# Roseta_Battery.net
KiCad netlist of a schematic drawn in Altium Designer
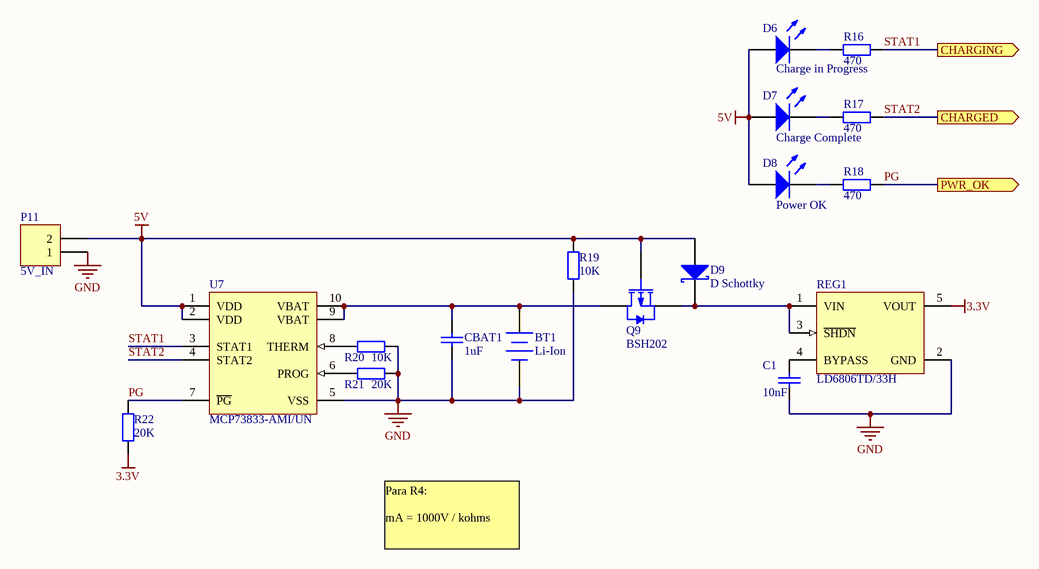
[diagram p0: Roseta_Battery.SchDoc]

(export (version "E")
  (design (tool "Eeschema 10.0.6"))
  (components
    (comp (ref "BT1")
      (value "Li-Ion")
      (footprint "BAT-2")
      (description "Multicell Battery")
      (fields (field (name "PUBLISHER") "Altium Limited"))
      (libsource (lib "Miscellaneous Devices") (part "Battery"))
    )
    (comp (ref "C1")
      (value "10nF")
      (footprint "1608[0603]")
      (description "Capacitor")
      (fields (field (name "Comment") "Cap") (field (name "PUBLISHER") "Altium Limited"))
      (libsource (lib "Miscellaneous Devices") (part "Cap"))
    )
    (comp (ref "CBAT1")
      (value "1uF")
      (footprint "1608[0603]")
      (description "Capacitor")
      (fields (field (name "Comment") "Cap") (field (name "PUBLISHER") "Altium Limited"))
      (libsource (lib "Miscellaneous Devices") (part "Cap"))
    )
    (comp (ref "D6")
      (value "Charge in Progress")
      (footprint "2013[0805]")
      (libsource (lib "LibreriaComponentes") (part "LED SMD (0603)"))
    )
    (comp (ref "D7")
      (value "Charge Complete")
      (footprint "2013[0805]")
      (libsource (lib "LibreriaComponentes") (part "LED SMD (0603)"))
    )
    (comp (ref "D8")
      (value "Power OK")
      (footprint "2013[0805]")
      (libsource (lib "LibreriaComponentes") (part "LED SMD (0603)"))
    )
    (comp (ref "D9")
      (value "D Schottky")
      (footprint "SOD123/X.85")
      (description "Schottky Diode")
      (fields (field (name "PUBLISHER") "Altium Limited"))
      (libsource (lib "Miscellaneous Devices") (part "D Schottky"))
    )
    (comp (ref "P11")
      (value "5V_IN")
      (footprint "HDR1X2")
      (description "Header, 2-Pin")
      (fields (field (name "PUBLISHER") "Altium Limited"))
      (libsource (lib "Miscellaneous Connectors") (part "Header 2"))
    )
    (comp (ref "Q9")
      (value "BSH202")
      (footprint "SOT95P240-3M")
      (description "P-channel Enhancement Mode MOSFET")
      (fields (field (name "PUBLISHER") "Altium Limited"))
      (libsource (lib "Philips Discrete MOSFET - Low Power") (part "BSH202"))
    )
    (comp (ref "R16")
      (value "470")
      (footprint "1608[0603]")
      (description "Resistor")
      (fields (field (name "Comment") "Res2") (field (name "PUBLISHER") "Altium Limited"))
      (libsource (lib "Miscellaneous Devices") (part "Res2"))
    )
    (comp (ref "R17")
      (value "470")
      (footprint "1608[0603]")
      (description "Resistor")
      (fields (field (name "Comment") "Res2") (field (name "PUBLISHER") "Altium Limited"))
      (libsource (lib "Miscellaneous Devices") (part "Res2"))
    )
    (comp (ref "R18")
      (value "470")
      (footprint "1608[0603]")
      (description "Resistor")
      (fields (field (name "Comment") "Res2") (field (name "PUBLISHER") "Altium Limited"))
      (libsource (lib "Miscellaneous Devices") (part "Res2"))
    )
    (comp (ref "R19")
      (value "10K")
      (footprint "1608[0603]")
      (description "Resistor")
      (fields (field (name "Comment") "Res2") (field (name "PUBLISHER") "Altium Limited"))
      (libsource (lib "") (part "Res2_1"))
    )
    (comp (ref "R20")
      (value "10K")
      (footprint "1608[0603]")
      (description "Resistor")
      (fields (field (name "Comment") "Res2") (field (name "PUBLISHER") "Altium Limited"))
      (libsource (lib "") (part "Res2_2"))
    )
    (comp (ref "R21")
      (value "20K")
      (footprint "1608[0603]")
      (description "Resistor")
      (fields (field (name "Comment") "Res2") (field (name "PUBLISHER") "Altium Limited"))
      (libsource (lib "") (part "Res2_2"))
    )
    (comp (ref "R22")
      (value "20K")
      (footprint "1608[0603]")
      (description "Resistor")
      (fields (field (name "Comment") "Res2") (field (name "PUBLISHER") "Altium Limited"))
      (libsource (lib "") (part "Res2_1"))
    )
    (comp (ref "REG1")
      (value "LD6806TD/33H")
      (footprint "SOT-23-OT5_N")
      (fields (field (name "PUBLISHER") "Altium Limited"))
      (libsource (lib "Microchip Power Mgt Line Regulator") (part "TC1014-1.8VCT713"))
    )
    (comp (ref "U7")
      (value "MCP73833-AMI/UN")
      (footprint "MSOP-UN10_N")
      (fields (field (name "PUBLISHER") "Altium Limited"))
      (libsource (lib "Microchip Power Mgt Battery Management") (part "MCP73833-AMI/UN"))
    )
  )
  (nets
    (net (code "1") (name "/PG") (class "Default")
      (node (ref "R18") (pin "2") (pinfunction "2_2") (pintype "passive"))
      (node (ref "R22") (pin "1") (pinfunction "1_1") (pintype "passive"))
      (node (ref "U7") (pin "7") (pinfunction "~{PG}_7") (pintype "open_collector"))
    )
    (net (code "2") (name "/STAT1") (class "Default")
      (node (ref "R16") (pin "2") (pinfunction "2_2") (pintype "passive"))
      (node (ref "U7") (pin "3") (pinfunction "STAT1_3") (pintype "open_collector"))
    )
    (net (code "3") (name "/STAT2") (class "Default")
      (node (ref "R17") (pin "2") (pinfunction "2_2") (pintype "passive"))
      (node (ref "U7") (pin "4") (pinfunction "STAT2_4") (pintype "open_collector"))
    )
    (net (code "4") (name "3.3V") (class "Default")
      (node (ref "R22") (pin "2") (pinfunction "2_2") (pintype "passive"))
      (node (ref "REG1") (pin "5") (pinfunction "VOUT_5") (pintype "power_in"))
    )
    (net (code "5") (name "5V") (class "Default")
      (node (ref "D6") (pin "1") (pinfunction "1_1") (pintype "passive"))
      (node (ref "D7") (pin "1") (pinfunction "1_1") (pintype "passive"))
      (node (ref "D8") (pin "1") (pinfunction "1_1") (pintype "passive"))
      (node (ref "D9") (pin "1") (pinfunction "A_1") (pintype "passive"))
      (node (ref "P11") (pin "2") (pinfunction "2_2") (pintype "passive"))
      (node (ref "Q9") (pin "1") (pinfunction "G_1") (pintype "passive"))
      (node (ref "R19") (pin "1") (pinfunction "1_1") (pintype "passive"))
      (node (ref "U7") (pin "1") (pinfunction "VDD_1") (pintype "power_in"))
      (node (ref "U7") (pin "2") (pinfunction "VDD_2") (pintype "power_in"))
    )
    (net (code "6") (name "GND") (class "Default")
      (node (ref "BT1") (pin "2") (pinfunction "-_2") (pintype "passive"))
      (node (ref "C1") (pin "1") (pinfunction "1_1") (pintype "passive"))
      (node (ref "CBAT1") (pin "2") (pinfunction "2_2") (pintype "passive"))
      (node (ref "P11") (pin "1") (pinfunction "1_1") (pintype "passive"))
      (node (ref "R19") (pin "2") (pinfunction "2_2") (pintype "passive"))
      (node (ref "R20") (pin "1") (pinfunction "1_1") (pintype "passive"))
      (node (ref "R21") (pin "1") (pinfunction "1_1") (pintype "passive"))
      (node (ref "REG1") (pin "2") (pinfunction "GND_2") (pintype "power_in"))
      (node (ref "U7") (pin "5") (pinfunction "VSS_5") (pintype "power_in"))
    )
    (net (code "7") (name "Net-(BT1-+)") (class "Default")
      (node (ref "BT1") (pin "1") (pinfunction "+_1") (pintype "passive"))
      (node (ref "CBAT1") (pin "1") (pinfunction "1_1") (pintype "passive"))
      (node (ref "Q9") (pin "3") (pinfunction "D_3") (pintype "passive"))
      (node (ref "U7") (pin "10") (pinfunction "VBAT_10") (pintype "power_in"))
      (node (ref "U7") (pin "9") (pinfunction "VBAT_9") (pintype "power_in"))
    )
    (net (code "8") (name "Net-(D6-Pad2)") (class "Default")
      (node (ref "D6") (pin "2") (pinfunction "2_2") (pintype "passive"))
      (node (ref "R16") (pin "1") (pinfunction "1_1") (pintype "passive"))
    )
    (net (code "9") (name "Net-(D7-Pad2)") (class "Default")
      (node (ref "D7") (pin "2") (pinfunction "2_2") (pintype "passive"))
      (node (ref "R17") (pin "1") (pinfunction "1_1") (pintype "passive"))
    )
    (net (code "10") (name "Net-(D8-Pad2)") (class "Default")
      (node (ref "D8") (pin "2") (pinfunction "2_2") (pintype "passive"))
      (node (ref "R18") (pin "1") (pinfunction "1_1") (pintype "passive"))
    )
    (net (code "11") (name "Net-(D9-K)") (class "Default")
      (node (ref "D9") (pin "2") (pinfunction "K_2") (pintype "passive"))
      (node (ref "Q9") (pin "2") (pinfunction "S_2") (pintype "passive"))
      (node (ref "REG1") (pin "1") (pinfunction "VIN_1") (pintype "power_in"))
      (node (ref "REG1") (pin "3") (pinfunction "~{SHDN}_3") (pintype "input"))
    )
    (net (code "12") (name "Net-(REG1-BYPASS)") (class "Default")
      (node (ref "C1") (pin "2") (pinfunction "2_2") (pintype "passive"))
      (node (ref "REG1") (pin "4") (pinfunction "BYPASS_4") (pintype "passive"))
    )
    (net (code "13") (name "Net-(U7-PROG)") (class "Default")
      (node (ref "R21") (pin "2") (pinfunction "2_2") (pintype "passive"))
      (node (ref "U7") (pin "6") (pinfunction "PROG_6") (pintype "input"))
    )
    (net (code "14") (name "Net-(U7-THERM)") (class "Default")
      (node (ref "R20") (pin "2") (pinfunction "2_2") (pintype "passive"))
      (node (ref "U7") (pin "8") (pinfunction "THERM_8") (pintype "input"))
    )
  )
)
